# AlarmTimer_Schematic.net
KiCad netlist of a schematic drawn in Altium Designer
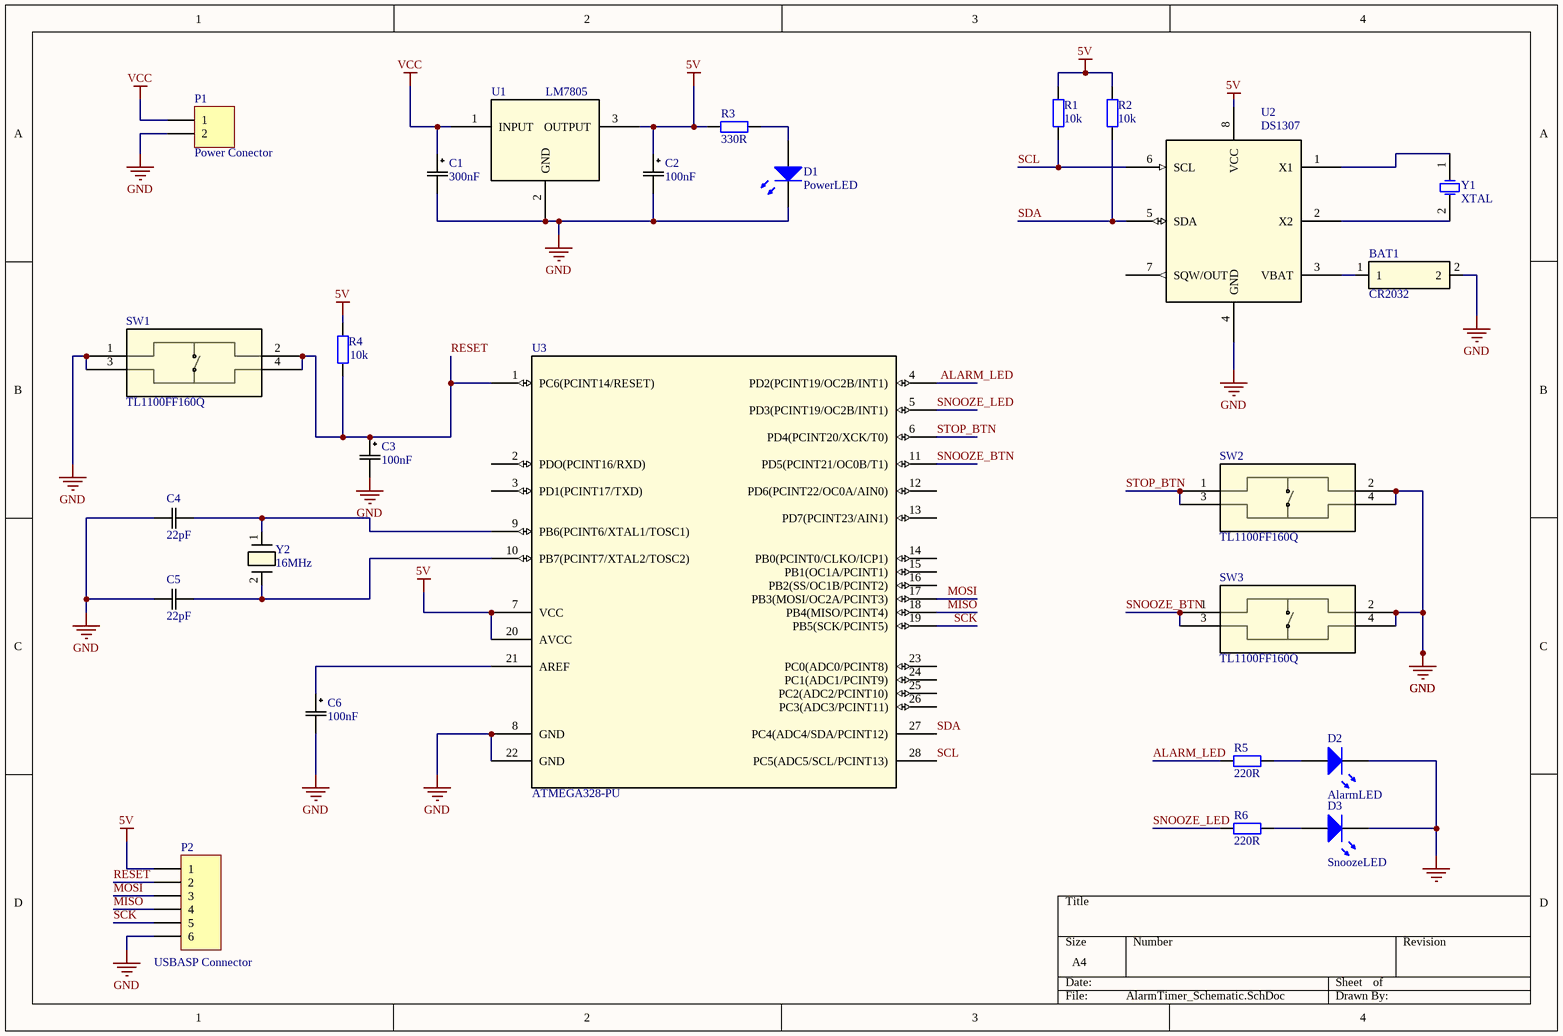
[diagram p0: AlarmTimer_Schematic.SchDoc]

(export (version "E")
  (design (tool "Eeschema 10.0.6"))
  (components
    (comp (ref "BAT1")
      (value "CR2032")
      (footprint "BAT_SMTU2032_RNB")
      (description "No Description Available")
      (fields
        (field (name "MANUFACTURER_PART_NUMBER") "SMTU2032")
        (field (name "COPYRIGHT") "Copyright (C) 2018 Accelerated Designs. All rights reserved")
      )
      (libsource (lib "CR2032_LiCell") (part "SMTU2032"))
    )
    (comp (ref "C1")
      (value "300nF")
      (footprint "CAP_UEP_5X11_NCH")
      (description "No Description Available")
      (fields
        (field (name "MANUFACTURER_PART_NUMBER") "UFW2A0R1MDD1TD")
        (field (name "COPYRIGHT") "Copyright (C) 2018 Accelerated Designs. All rights reserved")
      )
      (libsource (lib "Polarized Capacitor") (part "Cap Pol"))
    )
    (comp (ref "C2")
      (value "100nF")
      (footprint "CAP_UEP_5X11_NCH")
      (description "No Description Available")
      (fields
        (field (name "MANUFACTURER_PART_NUMBER") "UFW2A0R1MDD1TD")
        (field (name "COPYRIGHT") "Copyright (C) 2018 Accelerated Designs. All rights reserved")
      )
      (libsource (lib "Polarized Capacitor") (part "Cap Pol"))
    )
    (comp (ref "C3")
      (value "100nF")
      (footprint "CAP_UEP_5X11_NCH")
      (description "No Description Available")
      (fields
        (field (name "MANUFACTURER_PART_NUMBER") "UFW2A0R1MDD1TD")
        (field (name "COPYRIGHT") "Copyright (C) 2018 Accelerated Designs. All rights reserved")
      )
      (libsource (lib "Polarized Capacitor") (part "Cap Pol"))
    )
    (comp (ref "C4")
      (value "22pF")
      (footprint "CAP_FA28_TDK")
      (description "No Description Available")
      (fields
        (field (name "MANUFACTURER_PART_NUMBER") "FA28C0G1H220JNU00")
        (field (name "COPYRIGHT") "Copyright (C) 2018 Accelerated Designs. All rights reserved")
      )
      (libsource (lib "22pF Capacitor") (part "FA28C0G1H220JNU00"))
    )
    (comp (ref "C5")
      (value "22pF")
      (footprint "CAP_FA28_TDK")
      (description "No Description Available")
      (fields
        (field (name "MANUFACTURER_PART_NUMBER") "FA28C0G1H220JNU00")
        (field (name "COPYRIGHT") "Copyright (C) 2018 Accelerated Designs. All rights reserved")
      )
      (libsource (lib "22pF Capacitor") (part "FA28C0G1H220JNU00"))
    )
    (comp (ref "C6")
      (value "100nF")
      (footprint "CAP_UEP_5X11_NCH")
      (description "No Description Available")
      (fields
        (field (name "MANUFACTURER_PART_NUMBER") "UFW2A0R1MDD1TD")
        (field (name "COPYRIGHT") "Copyright (C) 2018 Accelerated Designs. All rights reserved")
      )
      (libsource (lib "Polarized Capacitor") (part "Cap Pol"))
    )
    (comp (ref "D1") (value "PowerLED") (footprint "LED") (libsource (lib "LED") (part "LED")))
    (comp (ref "D2") (value "AlarmLED") (footprint "LED") (libsource (lib "LED") (part "LED")))
    (comp (ref "D3") (value "SnoozeLED") (footprint "LED") (libsource (lib "LED") (part "LED")))
    (comp (ref "P1")
      (value "Power Conector")
      (footprint "HDR1X2H")
      (description "Header, 2-Pin, Right Angle")
      (fields (field (name "PUBLISHER") "Altium Limited"))
      (libsource (lib "Miscellaneous Connectors") (part "Header 2H"))
    )
    (comp (ref "P2")
      (value "USBASP Connector")
      (footprint "HDR1X6H")
      (description "Header, 6-Pin, Right Angle")
      (fields (field (name "PUBLISHER") "Altium Limited"))
      (libsource (lib "Miscellaneous Connectors") (part "Header 6H"))
    )
    (comp (ref "R1")
      (value "10k")
      (footprint "AXIAL-0.4")
      (description "Resistor")
      (fields (field (name "PUBLISHER") "Altium Limited"))
      (libsource (lib "") (part "Res2_1"))
    )
    (comp (ref "R2")
      (value "10k")
      (footprint "AXIAL-0.4")
      (description "Resistor")
      (fields (field (name "PUBLISHER") "Altium Limited"))
      (libsource (lib "") (part "Res2_1"))
    )
    (comp (ref "R3")
      (value "330R")
      (footprint "AXIAL-0.4")
      (description "Resistor")
      (fields (field (name "PUBLISHER") "Altium Limited"))
      (libsource (lib "Miscellaneous Devices") (part "Res2"))
    )
    (comp (ref "R4")
      (value "10k")
      (footprint "AXIAL-0.4")
      (description "Resistor")
      (fields (field (name "PUBLISHER") "Altium Limited"))
      (libsource (lib "") (part "Res2_2"))
    )
    (comp (ref "R5")
      (value "220R")
      (footprint "AXIAL-0.4")
      (description "Resistor")
      (fields (field (name "PUBLISHER") "Altium Limited"))
      (libsource (lib "Miscellaneous Devices") (part "Res2"))
    )
    (comp (ref "R6")
      (value "220R")
      (footprint "AXIAL-0.4")
      (description "Resistor")
      (fields (field (name "PUBLISHER") "Altium Limited"))
      (libsource (lib "Miscellaneous Devices") (part "Res2"))
    )
    (comp (ref "SW1")
      (value "TL1100FF160Q")
      (footprint "TL1100F")
      (description "No Description Available")
      (fields (field (name "COPYRIGHT") "Copyright (C) 2018 Accelerated Designs. All rights reserved"))
      (libsource (lib "TL1100 Tactile Switch") (part "TL1100FF160Q"))
    )
    (comp (ref "SW2")
      (value "TL1100FF160Q")
      (footprint "TL1100F")
      (description "No Description Available")
      (fields (field (name "COPYRIGHT") "Copyright (C) 2018 Accelerated Designs. All rights reserved"))
      (libsource (lib "TL1100 Tactile Switch") (part "TL1100FF160Q"))
    )
    (comp (ref "SW3")
      (value "TL1100FF160Q")
      (footprint "TL1100F")
      (description "No Description Available")
      (fields (field (name "COPYRIGHT") "Copyright (C) 2018 Accelerated Designs. All rights reserved"))
      (libsource (lib "TL1100 Tactile Switch") (part "TL1100FF160Q"))
    )
    (comp (ref "U1")
      (value "LM7805")
      (footprint "TO-220_FAS")
      (description "No Description Available")
      (fields
        (field (name "MANUFACTURER_PART_NUMBER") "LM7805CT")
        (field (name "COPYRIGHT") "Copyright (C) 2018 Accelerated Designs. All rights reserved")
      )
      (libsource (lib "LM7805") (part "LM7805CT"))
    )
    (comp (ref "U2")
      (value "DS1307")
      (footprint "21-0043D_8_MXM")
      (description "No Description Available")
      (fields
        (field (name "MANUFACTURER_PART_NUMBER") "DS1307+")
        (field (name "COPYRIGHT") "Copyright (C) 2018 Accelerated Designs. All rights reserved")
      )
      (libsource (lib "DS1307") (part "DS1307+"))
    )
    (comp (ref "U3")
      (value "ATMEGA328-PU")
      (footprint "28P3_SPDIP28_SP_MCH")
      (description "No Description Available")
      (fields (field (name "COPYRIGHT") "Copyright (C) 2018 Accelerated Designs. All rights reserved"))
      (libsource (lib "ATmega328PU") (part "ATMEGA328-PU"))
    )
    (comp (ref "Y1")
      (value "XTAL")
      (footprint "R38")
      (description "Crystal Oscillator")
      (fields (field (name "PUBLISHER") "Altium Limited"))
      (libsource (lib "Miscellaneous Devices") (part "XTAL"))
    )
    (comp (ref "Y2")
      (value "16MHz")
      (footprint "XTAL_ABL_ABR")
      (description "No Description Available")
      (fields
        (field (name "MANUFACTURER_PART_NUMBER") "ABL-20.000MHZ-B2")
        (field (name "COPYRIGHT") "Copyright (C) 2018 Accelerated Designs. All rights reserved")
      )
      (libsource (lib "16MHz crystal") (part "16MHz"))
    )
  )
  (nets
    (net (code "1") (name "/ALARM_LED") (class "Default")
      (node (ref "R5") (pin "1") (pinfunction "1_1") (pintype "passive"))
      (node (ref "U3") (pin "4") (pinfunction "PD2(PCINT19/OC2B/INT1)_4") (pintype "bidirectional"))
    )
    (net (code "2") (name "/MISO") (class "Default")
      (node (ref "P2") (pin "4") (pinfunction "4_4") (pintype "passive"))
      (node (ref "U3") (pin "18") (pinfunction "PB4(MISO/PCINT4)_18") (pintype "bidirectional"))
    )
    (net (code "3") (name "/MOSI") (class "Default")
      (node (ref "P2") (pin "3") (pinfunction "3_3") (pintype "passive"))
      (node (ref "U3") (pin "17") (pinfunction "PB3(MOSI/OC2A/PCINT3)_17") (pintype "bidirectional"))
    )
    (net (code "4") (name "/RESET") (class "Default")
      (node (ref "C3") (pin "1") (pinfunction "1_1") (pintype "passive"))
      (node (ref "P2") (pin "2") (pinfunction "2_2") (pintype "passive"))
      (node (ref "R4") (pin "1") (pinfunction "1_1") (pintype "passive"))
      (node (ref "SW1") (pin "2") (pinfunction "2_2") (pintype "passive"))
      (node (ref "SW1") (pin "4") (pinfunction "4_4") (pintype "passive"))
      (node (ref "U3") (pin "1") (pinfunction "PC6(PCINT14/RESET)_1") (pintype "bidirectional"))
    )
    (net (code "5") (name "/SCK") (class "Default")
      (node (ref "P2") (pin "5") (pinfunction "5_5") (pintype "passive"))
      (node (ref "U3") (pin "19") (pinfunction "PB5(SCK/PCINT5)_19") (pintype "bidirectional"))
    )
    (net (code "6") (name "/SCL") (class "Default")
      (node (ref "R1") (pin "2") (pinfunction "2_2") (pintype "passive"))
      (node (ref "U2") (pin "6") (pinfunction "SCL_6") (pintype "input"))
      (node (ref "U3") (pin "28") (pinfunction "PC5(ADC5/SCL/PCINT13)_28") (pintype "open_collector"))
    )
    (net (code "7") (name "/SDA") (class "Default")
      (node (ref "R2") (pin "2") (pinfunction "2_2") (pintype "passive"))
      (node (ref "U2") (pin "5") (pinfunction "SDA_5") (pintype "bidirectional"))
      (node (ref "U3") (pin "27") (pinfunction "PC4(ADC4/SDA/PCINT12)_27") (pintype "open_collector"))
    )
    (net (code "8") (name "/SNOOZE_BTN") (class "Default")
      (node (ref "SW3") (pin "1") (pinfunction "1_1") (pintype "passive"))
      (node (ref "SW3") (pin "3") (pinfunction "3_3") (pintype "passive"))
      (node (ref "U3") (pin "11") (pinfunction "PD5(PCINT21/OC0B/T1)_11") (pintype "bidirectional"))
    )
    (net (code "9") (name "/SNOOZE_LED") (class "Default")
      (node (ref "R6") (pin "1") (pinfunction "1_1") (pintype "passive"))
      (node (ref "U3") (pin "5") (pinfunction "PD3(PCINT19/OC2B/INT1)_5") (pintype "bidirectional"))
    )
    (net (code "10") (name "/STOP_BTN") (class "Default")
      (node (ref "SW2") (pin "1") (pinfunction "1_1") (pintype "passive"))
      (node (ref "SW2") (pin "3") (pinfunction "3_3") (pintype "passive"))
      (node (ref "U3") (pin "6") (pinfunction "PD4(PCINT20/XCK/T0)_6") (pintype "bidirectional"))
    )
    (net (code "11") (name "5V") (class "Default")
      (node (ref "C2") (pin "1") (pinfunction "1_1") (pintype "passive"))
      (node (ref "P2") (pin "1") (pinfunction "1_1") (pintype "passive"))
      (node (ref "R1") (pin "1") (pinfunction "1_1") (pintype "passive"))
      (node (ref "R2") (pin "1") (pinfunction "1_1") (pintype "passive"))
      (node (ref "R3") (pin "1") (pinfunction "1_1") (pintype "passive"))
      (node (ref "R4") (pin "2") (pinfunction "2_2") (pintype "passive"))
      (node (ref "U1") (pin "3") (pinfunction "OUTPUT_3") (pintype "power_in"))
      (node (ref "U2") (pin "8") (pinfunction "VCC_8") (pintype "power_in"))
      (node (ref "U3") (pin "20") (pinfunction "AVCC_20") (pintype "power_in"))
      (node (ref "U3") (pin "7") (pinfunction "VCC_7") (pintype "power_in"))
    )
    (net (code "12") (name "GND") (class "Default")
      (node (ref "BAT1") (pin "2") (pinfunction "2_2") (pintype "passive"))
      (node (ref "C1") (pin "2") (pinfunction "2_2") (pintype "passive"))
      (node (ref "C2") (pin "2") (pinfunction "2_2") (pintype "passive"))
      (node (ref "C3") (pin "2") (pinfunction "2_2") (pintype "passive"))
      (node (ref "C4") (pin "1") (pinfunction "1_1") (pintype "passive"))
      (node (ref "C5") (pin "1") (pinfunction "1_1") (pintype "passive"))
      (node (ref "C6") (pin "2") (pinfunction "2_2") (pintype "passive"))
      (node (ref "D1") (pin "1") (pinfunction "1_1") (pintype "passive"))
      (node (ref "D2") (pin "1") (pinfunction "1_1") (pintype "passive"))
      (node (ref "D3") (pin "1") (pinfunction "1_1") (pintype "passive"))
      (node (ref "P1") (pin "2") (pinfunction "2_2") (pintype "passive"))
      (node (ref "P2") (pin "6") (pinfunction "6_6") (pintype "passive"))
      (node (ref "SW1") (pin "1") (pinfunction "1_1") (pintype "passive"))
      (node (ref "SW1") (pin "3") (pinfunction "3_3") (pintype "passive"))
      (node (ref "SW2") (pin "2") (pinfunction "2_2") (pintype "passive"))
      (node (ref "SW2") (pin "4") (pinfunction "4_4") (pintype "passive"))
      (node (ref "SW3") (pin "2") (pinfunction "2_2") (pintype "passive"))
      (node (ref "SW3") (pin "4") (pinfunction "4_4") (pintype "passive"))
      (node (ref "U1") (pin "2") (pinfunction "GND_2") (pintype "power_in"))
      (node (ref "U2") (pin "4") (pinfunction "GND_4") (pintype "power_in"))
      (node (ref "U3") (pin "22") (pinfunction "GND_22") (pintype "passive"))
      (node (ref "U3") (pin "8") (pinfunction "GND_8") (pintype "passive"))
    )
    (net (code "13") (name "Net-(D1-Pad2)") (class "Default")
      (node (ref "D1") (pin "2") (pinfunction "2_2") (pintype "passive"))
      (node (ref "R3") (pin "2") (pinfunction "2_2") (pintype "passive"))
    )
    (net (code "14") (name "Net-(D2-Pad2)") (class "Default")
      (node (ref "D2") (pin "2") (pinfunction "2_2") (pintype "passive"))
      (node (ref "R5") (pin "2") (pinfunction "2_2") (pintype "passive"))
    )
    (net (code "15") (name "Net-(D3-Pad2)") (class "Default")
      (node (ref "D3") (pin "2") (pinfunction "2_2") (pintype "passive"))
      (node (ref "R6") (pin "2") (pinfunction "2_2") (pintype "passive"))
    )
    (net (code "16") (name "Net-(U2-VBAT)") (class "Default")
      (node (ref "BAT1") (pin "1") (pinfunction "1_1") (pintype "passive"))
      (node (ref "U2") (pin "3") (pinfunction "VBAT_3") (pintype "power_in"))
    )
    (net (code "17") (name "Net-(U2-X1)") (class "Default")
      (node (ref "U2") (pin "1") (pinfunction "X1_1") (pintype "passive"))
      (node (ref "Y1") (pin "1") (pinfunction "OSC1_1") (pintype "passive"))
    )
    (net (code "18") (name "Net-(U2-X2)") (class "Default")
      (node (ref "U2") (pin "2") (pinfunction "X2_2") (pintype "passive"))
      (node (ref "Y1") (pin "2") (pinfunction "OSC2_2") (pintype "passive"))
    )
    (net (code "19") (name "Net-(U3-AREF)") (class "Default")
      (node (ref "C6") (pin "1") (pinfunction "1_1") (pintype "passive"))
      (node (ref "U3") (pin "21") (pinfunction "AREF_21") (pintype "passive"))
    )
    (net (code "20") (name "Net-(U3-PB6(PCINT6{slash}XTAL1{slash}TOSC1))") (class "Default")
      (node (ref "C4") (pin "2") (pinfunction "2_2") (pintype "passive"))
      (node (ref "U3") (pin "9") (pinfunction "PB6(PCINT6/XTAL1/TOSC1)_9") (pintype "bidirectional"))
      (node (ref "Y2") (pin "1") (pinfunction "1_1") (pintype "passive"))
    )
    (net (code "21") (name "Net-(U3-PB7(PCINT7{slash}XTAL2{slash}TOSC2))") (class "Default")
      (node (ref "C5") (pin "2") (pinfunction "2_2") (pintype "passive"))
      (node (ref "U3") (pin "10") (pinfunction "PB7(PCINT7/XTAL2/TOSC2)_10") (pintype "bidirectional"))
      (node (ref "Y2") (pin "2") (pinfunction "2_2") (pintype "passive"))
    )
    (net (code "22") (name "VCC") (class "Default")
      (node (ref "C1") (pin "1") (pinfunction "1_1") (pintype "passive"))
      (node (ref "P1") (pin "1") (pinfunction "1_1") (pintype "passive"))
      (node (ref "U1") (pin "1") (pinfunction "INPUT_1") (pintype "power_in"))
    )
    (net (code "23") (name "unconnected-(U2-SQW{slash}OUT-Pad7)") (class "Default")
      (node (ref "U2") (pin "7") (pinfunction "SQW/OUT_7") (pintype "output"))
    )
    (net (code "24") (name "unconnected-(U3-PB0(PCINT0{slash}CLKO{slash}ICP1)-Pad14)") (class "Default")
      (node (ref "U3") (pin "14") (pinfunction "PB0(PCINT0/CLKO/ICP1)_14") (pintype "bidirectional"))
    )
    (net (code "25") (name "unconnected-(U3-PB1(OC1A{slash}PCINT1)-Pad15)") (class "Default")
      (node (ref "U3") (pin "15") (pinfunction "PB1(OC1A/PCINT1)_15") (pintype "bidirectional"))
    )
    (net (code "26") (name "unconnected-(U3-PB2(SS{slash}OC1B{slash}PCINT2)-Pad16)") (class "Default")
      (node (ref "U3") (pin "16") (pinfunction "PB2(SS/OC1B/PCINT2)_16") (pintype "bidirectional"))
    )
    (net (code "27") (name "unconnected-(U3-PC0(ADC0{slash}PCINT8)-Pad23)") (class "Default")
      (node (ref "U3") (pin "23") (pinfunction "PC0(ADC0/PCINT8)_23") (pintype "bidirectional"))
    )
    (net (code "28") (name "unconnected-(U3-PC1(ADC1{slash}PCINT9)-Pad24)") (class "Default")
      (node (ref "U3") (pin "24") (pinfunction "PC1(ADC1/PCINT9)_24") (pintype "bidirectional"))
    )
    (net (code "29") (name "unconnected-(U3-PC2(ADC2{slash}PCINT10)-Pad25)") (class "Default")
      (node (ref "U3") (pin "25") (pinfunction "PC2(ADC2/PCINT10)_25") (pintype "bidirectional"))
    )
    (net (code "30") (name "unconnected-(U3-PC3(ADC3{slash}PCINT11)-Pad26)") (class "Default")
      (node (ref "U3") (pin "26") (pinfunction "PC3(ADC3/PCINT11)_26") (pintype "bidirectional"))
    )
    (net (code "31") (name "unconnected-(U3-PD1(PCINT17{slash}TXD)-Pad3)") (class "Default")
      (node (ref "U3") (pin "3") (pinfunction "PD1(PCINT17/TXD)_3") (pintype "bidirectional"))
    )
    (net (code "32") (name "unconnected-(U3-PD6(PCINT22{slash}OC0A{slash}AIN0)-Pad12)") (class "Default")
      (node (ref "U3") (pin "12") (pinfunction "PD6(PCINT22/OC0A/AIN0)_12") (pintype "bidirectional"))
    )
    (net (code "33") (name "unconnected-(U3-PD7(PCINT23{slash}AIN1)-Pad13)") (class "Default")
      (node (ref "U3") (pin "13") (pinfunction "PD7(PCINT23/AIN1)_13") (pintype "bidirectional"))
    )
    (net (code "34") (name "unconnected-(U3-PDO(PCINT16{slash}RXD)-Pad2)") (class "Default")
      (node (ref "U3") (pin "2") (pinfunction "PDO(PCINT16/RXD)_2") (pintype "bidirectional"))
    )
  )
)
